# PIC18F27K42-I_ML.net
KiCad netlist of a schematic drawn in Altium Designer
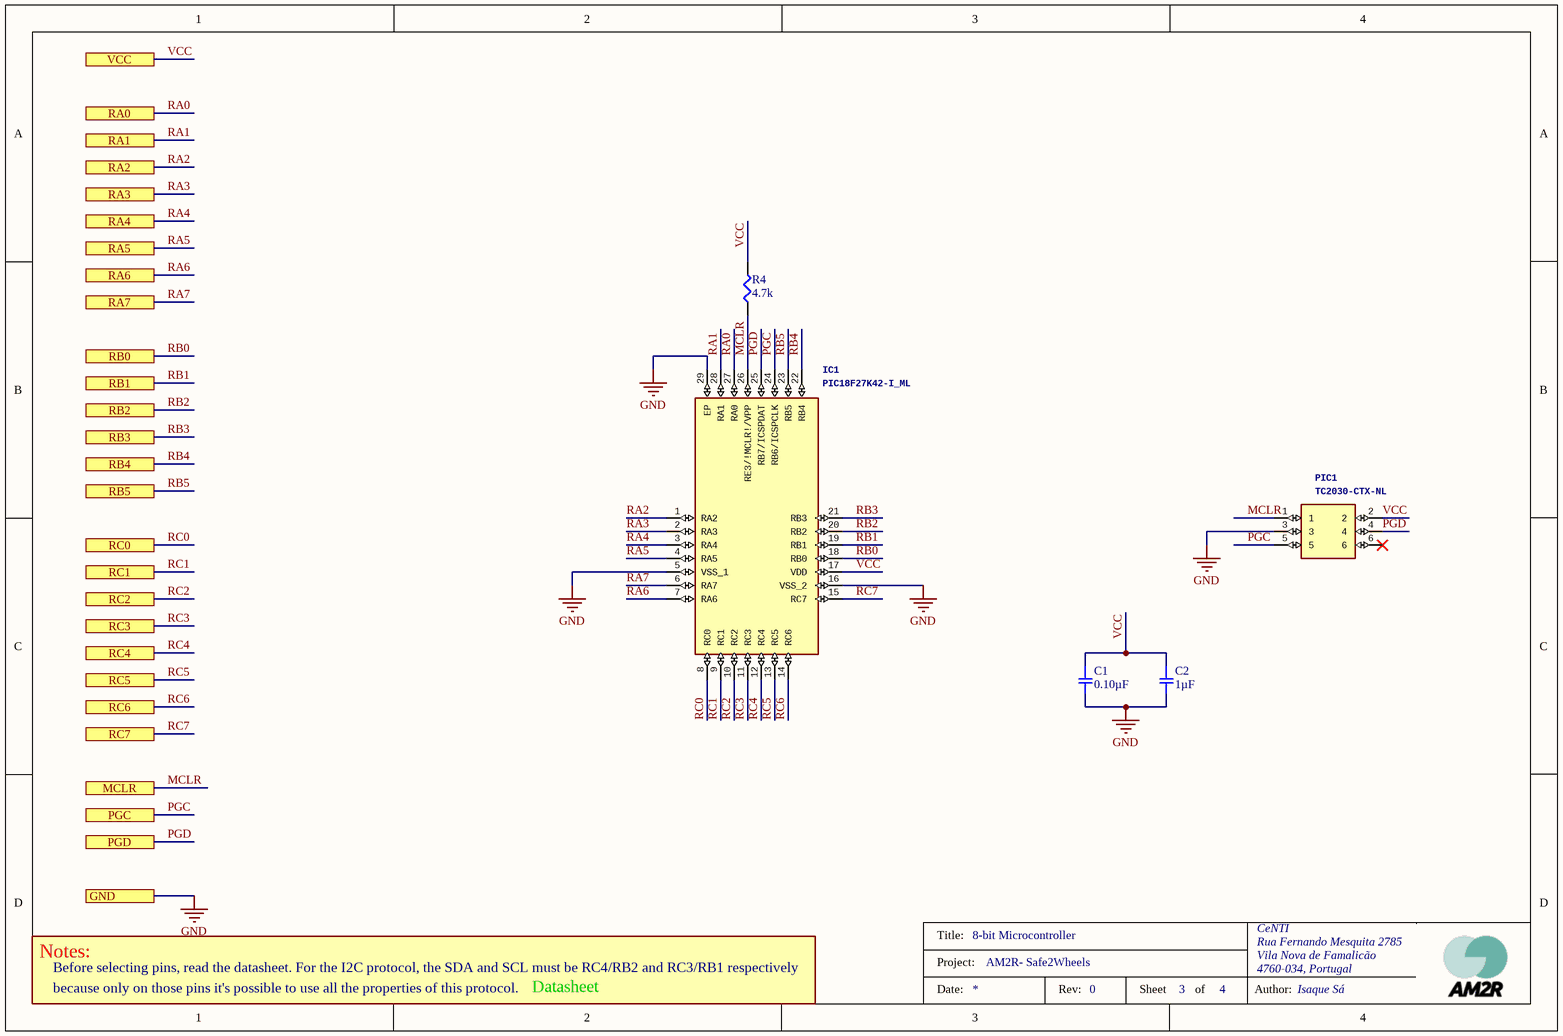
[diagram p0: PIC18F27K42-I_ML.SchDoc]

(export (version "E")
  (design (tool "Eeschema 10.0.6"))
  (components
    (comp (ref "C1")
      (value "0.10µF")
      (footprint "SMD-0402C")
      (description "CAP CER 0.1UF 16V X7R 0402")
      (fields
        (field (name "DIGI-KEY PART NUMBER") "490-4759-1-ND")
        (field (name "PART NUMBER") "GCM155R71C104KA55D")
      )
      (libsource (lib "capacitor_murata_0402") (part "GCM155R71C104KA55D"))
    )
    (comp (ref "C2")
      (value "1µF")
      (footprint "SMD-0402C")
      (description "CAP CER 1UF 10V X7S 0402")
      (fields
        (field (name "DIGI-KEY PART NUMBER") "490-13409-1-ND")
        (field (name "PART NUMBER") "GCM155C71A105KE38D")
      )
      (libsource (lib "capacitor_murata_0402") (part "GCM155C71A105KE38D"))
    )
    (comp (ref "IC1")
      (value "PIC18F27K42-I_ML")
      (footprint "QFN28_6x6")
      (description "8-bit Microcontrollers")
      (fields
        (field (name "MANUFACTURER_PART_NUMBER") "PIC18F27K42-I/ML")
        (field (name "MOUSER_PART_NUMBER") "579-PIC18F27K42-I/ML")
      )
      (libsource (lib "HW-General-Lib") (part "PIC18F27K42-I_ML"))
    )
    (comp (ref "PIC1")
      (value "TC2030-CTX-NL")
      (footprint "TC2030")
      (description "6-Pin \"No Legs\" Cable with 10-pin micro-connector for Cortex processors")
      (libsource (lib "HW-General-Lib") (part "TC2030-CTX-NL"))
    )
    (comp (ref "R4")
      (value "4.7k")
      (footprint "SMD-0402-RES")
      (description "RES SMD 4.7K OHM 1% 1/10W 0402")
      (fields
        (field (name "PART NUMBER") "ERJ-2RKF4701X")
        (field (name "DIGI-KEY PART NUMBER") "P4.70KLCT-ND")
      )
      (libsource (lib "Panasonic_ERJ_0402") (part "ERJ-2RKF4701X"))
    )
  )
  (nets
    (net (code "1") (name "/MCLR") (class "Default")
      (node (ref "IC1") (pin "26") (pinfunction "RE3/!MCLR!/VPP_26") (pintype "bidirectional"))
      (node (ref "PIC1") (pin "1") (pinfunction "1_1") (pintype "bidirectional"))
      (node (ref "R4") (pin "1") (pinfunction "1_1") (pintype "passive"))
    )
    (net (code "2") (name "/PGC") (class "Default")
      (node (ref "IC1") (pin "24") (pinfunction "RB6/ICSPCLK_24") (pintype "bidirectional"))
      (node (ref "PIC1") (pin "5") (pinfunction "5_5") (pintype "bidirectional"))
    )
    (net (code "3") (name "/PGD") (class "Default")
      (node (ref "IC1") (pin "25") (pinfunction "RB7/ICSPDAT_25") (pintype "bidirectional"))
      (node (ref "PIC1") (pin "4") (pinfunction "4_4") (pintype "bidirectional"))
    )
    (net (code "4") (name "/RA0") (class "Default")
      (node (ref "IC1") (pin "27") (pinfunction "RA0_27") (pintype "bidirectional"))
    )
    (net (code "5") (name "/RA1") (class "Default")
      (node (ref "IC1") (pin "28") (pinfunction "RA1_28") (pintype "bidirectional"))
    )
    (net (code "6") (name "/RA2") (class "Default")
      (node (ref "IC1") (pin "1") (pinfunction "RA2_1") (pintype "bidirectional"))
    )
    (net (code "7") (name "/RA3") (class "Default")
      (node (ref "IC1") (pin "2") (pinfunction "RA3_2") (pintype "bidirectional"))
    )
    (net (code "8") (name "/RA4") (class "Default")
      (node (ref "IC1") (pin "3") (pinfunction "RA4_3") (pintype "bidirectional"))
    )
    (net (code "9") (name "/RA5") (class "Default")
      (node (ref "IC1") (pin "4") (pinfunction "RA5_4") (pintype "bidirectional"))
    )
    (net (code "10") (name "/RA6") (class "Default")
      (node (ref "IC1") (pin "7") (pinfunction "RA6_7") (pintype "bidirectional"))
    )
    (net (code "11") (name "/RA7") (class "Default")
      (node (ref "IC1") (pin "6") (pinfunction "RA7_6") (pintype "bidirectional"))
    )
    (net (code "12") (name "/RB0") (class "Default")
      (node (ref "IC1") (pin "18") (pinfunction "RB0_18") (pintype "bidirectional"))
    )
    (net (code "13") (name "/RB1") (class "Default")
      (node (ref "IC1") (pin "19") (pinfunction "RB1_19") (pintype "bidirectional"))
    )
    (net (code "14") (name "/RB2") (class "Default")
      (node (ref "IC1") (pin "20") (pinfunction "RB2_20") (pintype "bidirectional"))
    )
    (net (code "15") (name "/RB3") (class "Default")
      (node (ref "IC1") (pin "21") (pinfunction "RB3_21") (pintype "bidirectional"))
    )
    (net (code "16") (name "/RB4") (class "Default")
      (node (ref "IC1") (pin "22") (pinfunction "RB4_22") (pintype "bidirectional"))
    )
    (net (code "17") (name "/RB5") (class "Default")
      (node (ref "IC1") (pin "23") (pinfunction "RB5_23") (pintype "bidirectional"))
    )
    (net (code "18") (name "/RC0") (class "Default")
      (node (ref "IC1") (pin "8") (pinfunction "RC0_8") (pintype "bidirectional"))
    )
    (net (code "19") (name "/RC1") (class "Default")
      (node (ref "IC1") (pin "9") (pinfunction "RC1_9") (pintype "bidirectional"))
    )
    (net (code "20") (name "/RC2") (class "Default")
      (node (ref "IC1") (pin "10") (pinfunction "RC2_10") (pintype "bidirectional"))
    )
    (net (code "21") (name "/RC3") (class "Default")
      (node (ref "IC1") (pin "11") (pinfunction "RC3_11") (pintype "bidirectional"))
    )
    (net (code "22") (name "/RC4") (class "Default")
      (node (ref "IC1") (pin "12") (pinfunction "RC4_12") (pintype "bidirectional"))
    )
    (net (code "23") (name "/RC5") (class "Default")
      (node (ref "IC1") (pin "13") (pinfunction "RC5_13") (pintype "bidirectional"))
    )
    (net (code "24") (name "/RC6") (class "Default")
      (node (ref "IC1") (pin "14") (pinfunction "RC6_14") (pintype "bidirectional"))
    )
    (net (code "25") (name "/RC7") (class "Default")
      (node (ref "IC1") (pin "15") (pinfunction "RC7_15") (pintype "bidirectional"))
    )
    (net (code "26") (name "/VCC") (class "Default")
      (node (ref "C1") (pin "1") (pinfunction "1_1") (pintype "passive"))
      (node (ref "C2") (pin "1") (pinfunction "1_1") (pintype "passive"))
      (node (ref "IC1") (pin "17") (pinfunction "VDD_17") (pintype "bidirectional"))
      (node (ref "PIC1") (pin "2") (pinfunction "2_2") (pintype "bidirectional"))
      (node (ref "R4") (pin "2") (pinfunction "2_2") (pintype "passive"))
    )
    (net (code "27") (name "GND") (class "Default")
      (node (ref "C1") (pin "2") (pinfunction "2_2") (pintype "passive"))
      (node (ref "C2") (pin "2") (pinfunction "2_2") (pintype "passive"))
      (node (ref "IC1") (pin "16") (pinfunction "VSS_2_16") (pintype "bidirectional"))
      (node (ref "IC1") (pin "29") (pinfunction "EP_29") (pintype "bidirectional"))
      (node (ref "IC1") (pin "5") (pinfunction "VSS_1_5") (pintype "bidirectional"))
      (node (ref "PIC1") (pin "3") (pinfunction "3_3") (pintype "bidirectional"))
    )
    (net (code "28") (name "unconnected-(PIC1-Pad6)") (class "Default")
      (node (ref "PIC1") (pin "6") (pinfunction "6_6") (pintype "bidirectional+no_connect"))
    )
  )
)
